# placa_sensor1.net
KiCad netlist of a schematic drawn in EAGLE
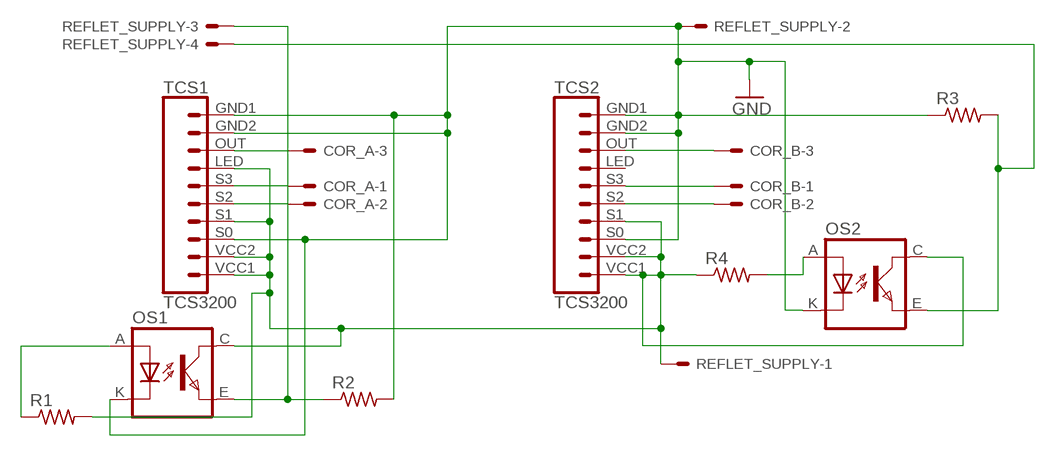
[diagram p0: schematic, sheet 1]

(export (version "E")
  (design (tool "Eeschema 10.0.6"))
  (components
    (comp (ref "COR_A")
      (value "22-05-7038-03")
      (footprint "eagle-import:7395-03")
      (libsource (lib "eagle-import") (part "22-?-0305-7038"))
    )
    (comp (ref "COR_B")
      (value "22-05-7038-03")
      (footprint "eagle-import:7395-03")
      (libsource (lib "eagle-import") (part "22-?-0305-7038"))
    )
    (comp (ref "OS1")
      (value "TCRT5000")
      (footprint "eagle-import:TCRT5000")
      (libsource (lib "eagle-import") (part "TCRT5000"))
    )
    (comp (ref "OS2")
      (value "TCRT5000")
      (footprint "eagle-import:TCRT5000")
      (libsource (lib "eagle-import") (part "TCRT5000"))
    )
    (comp (ref "R1")
      (value "R-US_0204/5")
      (footprint "eagle-import:0204_5")
      (libsource (lib "eagle-import") (part "R-US_0204/5"))
    )
    (comp (ref "R2")
      (value "R-US_0204/5")
      (footprint "eagle-import:0204_5")
      (libsource (lib "eagle-import") (part "R-US_0204/5"))
    )
    (comp (ref "R3")
      (value "R-US_0204/5")
      (footprint "eagle-import:0204_5")
      (libsource (lib "eagle-import") (part "R-US_0204/5"))
    )
    (comp (ref "R4")
      (value "R-US_0204/5")
      (footprint "eagle-import:0204_5")
      (libsource (lib "eagle-import") (part "R-US_0204/5"))
    )
    (comp (ref "REFLET_SUPPLY")
      (value "22-05-7048-04")
      (footprint "eagle-import:7395-04")
      (libsource (lib "eagle-import") (part "22-?-0405-7048"))
    )
    (comp (ref "TCS1")
      (value "TCS3200")
      (footprint "eagle-import:TCS3200")
      (libsource (lib "eagle-import") (part "TCS3200"))
    )
    (comp (ref "TCS2")
      (value "TCS3200")
      (footprint "eagle-import:TCS3200")
      (libsource (lib "eagle-import") (part "TCS3200"))
    )
  )
  (nets
    (net (code "1") (name "GND") (class "Default")
      (node (ref "OS1") (pin "K") (pinfunction "CATHODE_K") (pintype "passive"))
      (node (ref "OS2") (pin "K") (pinfunction "CATHODE_K") (pintype "passive"))
      (node (ref "R2") (pin "2") (pinfunction "2_2") (pintype "passive"))
      (node (ref "R3") (pin "1") (pinfunction "1_1") (pintype "passive"))
      (node (ref "REFLET_SUPPLY") (pin "2") (pinfunction "S_2") (pintype "passive"))
      (node (ref "TCS1") (pin "GND1") (pinfunction "GND1_GND1") (pintype "passive"))
      (node (ref "TCS1") (pin "GND2") (pinfunction "GND2_GND2") (pintype "passive"))
      (node (ref "TCS1") (pin "S0") (pinfunction "S0_S0") (pintype "passive"))
      (node (ref "TCS2") (pin "GND1") (pinfunction "GND1_GND1") (pintype "passive"))
      (node (ref "TCS2") (pin "GND2") (pinfunction "GND2_GND2") (pintype "passive"))
      (node (ref "TCS2") (pin "S0") (pinfunction "S0_S0") (pintype "passive"))
    )
    (net (code "2") (name "Net-(COR_AA-S)") (class "Default")
      (node (ref "COR_A") (pin "1") (pinfunction "S_1") (pintype "passive"))
      (node (ref "TCS1") (pin "S3") (pinfunction "S3_S3") (pintype "passive"))
    )
    (net (code "3") (name "Net-(COR_AB-S)") (class "Default")
      (node (ref "COR_A") (pin "2") (pinfunction "S_2") (pintype "passive"))
      (node (ref "TCS1") (pin "S2") (pinfunction "S2_S2") (pintype "passive"))
    )
    (net (code "4") (name "Net-(COR_AC-S)") (class "Default")
      (node (ref "COR_A") (pin "3") (pinfunction "S_3") (pintype "passive"))
      (node (ref "TCS1") (pin "OUT") (pinfunction "OUT_OUT") (pintype "passive"))
    )
    (net (code "5") (name "Net-(COR_BA-S)") (class "Default")
      (node (ref "COR_B") (pin "1") (pinfunction "S_1") (pintype "passive"))
      (node (ref "TCS2") (pin "S3") (pinfunction "S3_S3") (pintype "passive"))
    )
    (net (code "6") (name "Net-(COR_BB-S)") (class "Default")
      (node (ref "COR_B") (pin "2") (pinfunction "S_2") (pintype "passive"))
      (node (ref "TCS2") (pin "S2") (pinfunction "S2_S2") (pintype "passive"))
    )
    (net (code "7") (name "Net-(COR_BC-S)") (class "Default")
      (node (ref "COR_B") (pin "3") (pinfunction "S_3") (pintype "passive"))
      (node (ref "TCS2") (pin "OUT") (pinfunction "OUT_OUT") (pintype "passive"))
    )
    (net (code "8") (name "Net-(OS1-ANODE)") (class "Default")
      (node (ref "OS1") (pin "A") (pinfunction "ANODE_A") (pintype "passive"))
      (node (ref "R1") (pin "1") (pinfunction "1_1") (pintype "passive"))
    )
    (net (code "9") (name "Net-(OS1-COLLECTOR)") (class "Default")
      (node (ref "OS1") (pin "C") (pinfunction "COLLECTOR_C") (pintype "passive"))
      (node (ref "OS2") (pin "C") (pinfunction "COLLECTOR_C") (pintype "passive"))
      (node (ref "R1") (pin "2") (pinfunction "2_2") (pintype "passive"))
      (node (ref "R4") (pin "1") (pinfunction "1_1") (pintype "passive"))
      (node (ref "REFLET_SUPPLY") (pin "1") (pinfunction "S_1") (pintype "passive"))
      (node (ref "TCS1") (pin "LED") (pinfunction "LED_LED") (pintype "passive"))
      (node (ref "TCS1") (pin "S1") (pinfunction "S1_S1") (pintype "passive"))
      (node (ref "TCS1") (pin "VCC1") (pinfunction "VCC1_VCC1") (pintype "passive"))
      (node (ref "TCS1") (pin "VCC2") (pinfunction "VCC2_VCC2") (pintype "passive"))
      (node (ref "TCS2") (pin "S1") (pinfunction "S1_S1") (pintype "passive"))
      (node (ref "TCS2") (pin "VCC1") (pinfunction "VCC1_VCC1") (pintype "passive"))
      (node (ref "TCS2") (pin "VCC2") (pinfunction "VCC2_VCC2") (pintype "passive"))
    )
    (net (code "10") (name "Net-(OS1-EMITTER)") (class "Default")
      (node (ref "OS1") (pin "E") (pinfunction "EMITTER_E") (pintype "passive"))
      (node (ref "R2") (pin "1") (pinfunction "1_1") (pintype "passive"))
      (node (ref "REFLET_SUPPLY") (pin "3") (pinfunction "S_3") (pintype "passive"))
    )
    (net (code "11") (name "Net-(OS2-ANODE)") (class "Default")
      (node (ref "OS2") (pin "A") (pinfunction "ANODE_A") (pintype "passive"))
      (node (ref "R4") (pin "2") (pinfunction "2_2") (pintype "passive"))
    )
    (net (code "12") (name "Net-(OS2-EMITTER)") (class "Default")
      (node (ref "OS2") (pin "E") (pinfunction "EMITTER_E") (pintype "passive"))
      (node (ref "R3") (pin "2") (pinfunction "2_2") (pintype "passive"))
      (node (ref "REFLET_SUPPLY") (pin "4") (pinfunction "S_4") (pintype "passive"))
    )
    (net (code "13") (name "unconnected-(TCS2-PadLED)") (class "Default")
      (node (ref "TCS2") (pin "LED") (pinfunction "LED_LED") (pintype "passive"))
    )
  )
)
